# VGA-OSCI_SMD.net
KiCad netlist of a schematic drawn in EAGLE
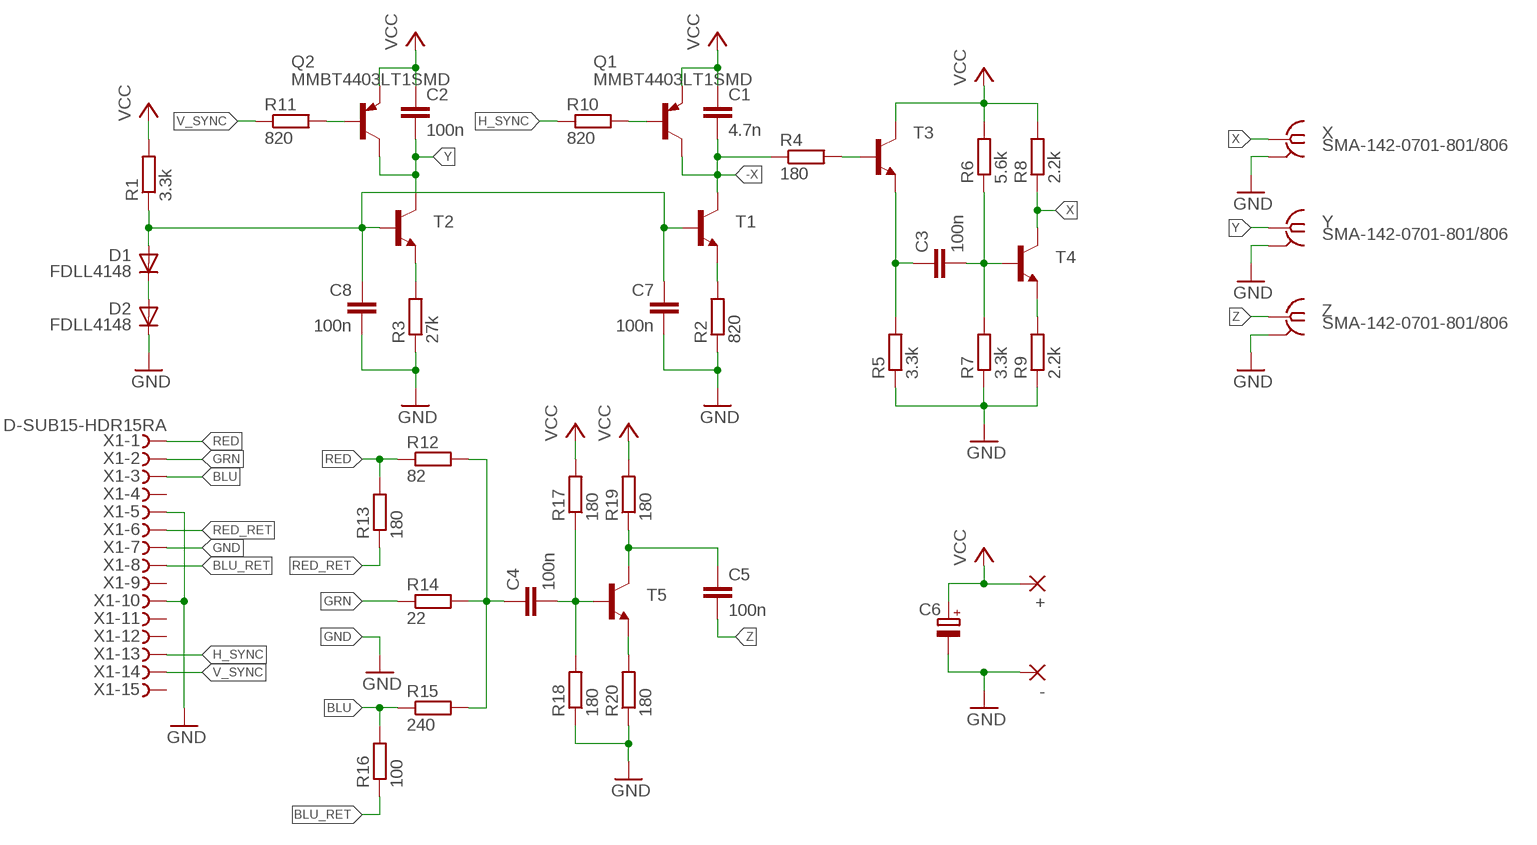
[diagram p0: schematic, sheet 1]

(export (version "E")
  (design (tool "Eeschema 10.0.6"))
  (components
    (comp (ref "+")
      (value "WIREPADSMD1,27-254")
      (footprint "eagle-import:SMD1,27-2,54")
      (libsource (lib "eagle-import") (part "WIREPADSMD1,27-254"))
    )
    (comp (ref "-")
      (value "WIREPADSMD1,27-254")
      (footprint "eagle-import:SMD1,27-2,54")
      (libsource (lib "eagle-import") (part "WIREPADSMD1,27-254"))
    )
    (comp (ref "C1")
      (value "4.7n")
      (footprint "eagle-import:C0603")
      (libsource (lib "eagle-import") (part "C-EUC0603"))
    )
    (comp (ref "C2")
      (value "100n")
      (footprint "eagle-import:C0603")
      (libsource (lib "eagle-import") (part "C-EUC0603"))
    )
    (comp (ref "C3")
      (value "100n")
      (footprint "eagle-import:C0603")
      (libsource (lib "eagle-import") (part "C-EUC0603"))
    )
    (comp (ref "C4")
      (value "100n")
      (footprint "eagle-import:C0603")
      (libsource (lib "eagle-import") (part "C-EUC0603"))
    )
    (comp (ref "C5")
      (value "100n")
      (footprint "eagle-import:C0603")
      (libsource (lib "eagle-import") (part "C-EUC0603"))
    )
    (comp (ref "C6")
      (value "CPOL-EU153CLV-0810")
      (footprint "eagle-import:153CLV-0810")
      (libsource (lib "eagle-import") (part "CPOL-EU153CLV-0810"))
    )
    (comp (ref "C7")
      (value "100n")
      (footprint "eagle-import:C0603")
      (libsource (lib "eagle-import") (part "C-EUC0603"))
    )
    (comp (ref "C8")
      (value "100n")
      (footprint "eagle-import:C0603")
      (libsource (lib "eagle-import") (part "C-EUC0603"))
    )
    (comp (ref "D1")
      (value "FDLL4148")
      (footprint "eagle-import:SOD80C")
      (libsource (lib "eagle-import") (part "DIODE-SOD80C"))
    )
    (comp (ref "D2")
      (value "FDLL4148")
      (footprint "eagle-import:SOD80C")
      (libsource (lib "eagle-import") (part "DIODE-SOD80C"))
    )
    (comp (ref "Q1")
      (value "MMBT4403LT1SMD")
      (footprint "eagle-import:SOT23-BEC")
      (libsource (lib "eagle-import") (part "-PNP-SOT23-BECMMBT4403LT1"))
    )
    (comp (ref "Q2")
      (value "MMBT4403LT1SMD")
      (footprint "eagle-import:SOT23-BEC")
      (libsource (lib "eagle-import") (part "-PNP-SOT23-BECMMBT4403LT1"))
    )
    (comp (ref "R1")
      (value "3.3k")
      (footprint "eagle-import:R0603")
      (libsource (lib "eagle-import") (part "R-EU_R0603"))
    )
    (comp (ref "R2")
      (value "820")
      (footprint "eagle-import:R0603")
      (libsource (lib "eagle-import") (part "R-EU_R0603"))
    )
    (comp (ref "R3")
      (value "27k")
      (footprint "eagle-import:R0603")
      (libsource (lib "eagle-import") (part "R-EU_R0603"))
    )
    (comp (ref "R4")
      (value "180")
      (footprint "eagle-import:R0603")
      (libsource (lib "eagle-import") (part "R-EU_R0603"))
    )
    (comp (ref "R5")
      (value "3.3k")
      (footprint "eagle-import:R0603")
      (libsource (lib "eagle-import") (part "R-EU_R0603"))
    )
    (comp (ref "R6")
      (value "5.6k")
      (footprint "eagle-import:R0603")
      (libsource (lib "eagle-import") (part "R-EU_R0603"))
    )
    (comp (ref "R7")
      (value "3.3k")
      (footprint "eagle-import:R0603")
      (libsource (lib "eagle-import") (part "R-EU_R0603"))
    )
    (comp (ref "R8")
      (value "2.2k")
      (footprint "eagle-import:R0603")
      (libsource (lib "eagle-import") (part "R-EU_R0603"))
    )
    (comp (ref "R9")
      (value "2.2k")
      (footprint "eagle-import:R0603")
      (libsource (lib "eagle-import") (part "R-EU_R0603"))
    )
    (comp (ref "R10")
      (value "820")
      (footprint "eagle-import:R0603")
      (libsource (lib "eagle-import") (part "R-EU_R0603"))
    )
    (comp (ref "R11")
      (value "820")
      (footprint "eagle-import:R0603")
      (libsource (lib "eagle-import") (part "R-EU_R0603"))
    )
    (comp (ref "R12")
      (value "82")
      (footprint "eagle-import:R0603")
      (libsource (lib "eagle-import") (part "R-EU_R0603"))
    )
    (comp (ref "R13")
      (value "180")
      (footprint "eagle-import:R0603")
      (libsource (lib "eagle-import") (part "R-EU_R0603"))
    )
    (comp (ref "R14")
      (value "22")
      (footprint "eagle-import:R0603")
      (libsource (lib "eagle-import") (part "R-EU_R0603"))
    )
    (comp (ref "R15")
      (value "240")
      (footprint "eagle-import:R0603")
      (libsource (lib "eagle-import") (part "R-EU_R0603"))
    )
    (comp (ref "R16")
      (value "100")
      (footprint "eagle-import:R0603")
      (libsource (lib "eagle-import") (part "R-EU_R0603"))
    )
    (comp (ref "R17")
      (value "180")
      (footprint "eagle-import:R0603")
      (libsource (lib "eagle-import") (part "R-EU_R0603"))
    )
    (comp (ref "R18")
      (value "180")
      (footprint "eagle-import:R0603")
      (libsource (lib "eagle-import") (part "R-EU_R0603"))
    )
    (comp (ref "R19")
      (value "180")
      (footprint "eagle-import:R0603")
      (libsource (lib "eagle-import") (part "R-EU_R0603"))
    )
    (comp (ref "R20")
      (value "180")
      (footprint "eagle-import:R0603")
      (libsource (lib "eagle-import") (part "R-EU_R0603"))
    )
    (comp (ref "T1")
      (value "MMBT2222ALT1-NPN-SOT23-BEC")
      (footprint "eagle-import:SOT23-BEC")
      (libsource (lib "eagle-import") (part "-NPN-SOT23-BECMMBT2222ALT1"))
    )
    (comp (ref "T2")
      (value "MMBT2222ALT1-NPN-SOT23-BEC")
      (footprint "eagle-import:SOT23-BEC")
      (libsource (lib "eagle-import") (part "-NPN-SOT23-BECMMBT2222ALT1"))
    )
    (comp (ref "T3")
      (value "MMBT2222ALT1-NPN-SOT23-BEC")
      (footprint "eagle-import:SOT23-BEC")
      (libsource (lib "eagle-import") (part "-NPN-SOT23-BECMMBT2222ALT1"))
    )
    (comp (ref "T4")
      (value "MMBT2222ALT1-NPN-SOT23-BEC")
      (footprint "eagle-import:SOT23-BEC")
      (libsource (lib "eagle-import") (part "-NPN-SOT23-BECMMBT2222ALT1"))
    )
    (comp (ref "T5")
      (value "MMBT2222ALT1-NPN-SOT23-BEC")
      (footprint "eagle-import:SOT23-BEC")
      (libsource (lib "eagle-import") (part "-NPN-SOT23-BECMMBT2222ALT1"))
    )
    (comp (ref "X")
      (value "SMA-142-0701-801/806")
      (footprint "eagle-import:J502-ND-142-0701-801_806")
      (fields (field (name "MF") "JOHNSON COMPONENTS") (field (name "MPN") "142-0701-801"))
      (libsource (lib "eagle-import") (part "SMA-142-0701-801/806"))
    )
    (comp (ref "X1")
      (value "D-SUB15-HDR15RA")
      (footprint "eagle-import:HDR15RA")
      (libsource (lib "eagle-import") (part "D-SUB15-HDR15RA"))
    )
    (comp (ref "Y")
      (value "SMA-142-0701-801/806")
      (footprint "eagle-import:J502-ND-142-0701-801_806")
      (fields (field (name "MF") "JOHNSON COMPONENTS") (field (name "MPN") "142-0701-801"))
      (libsource (lib "eagle-import") (part "SMA-142-0701-801/806"))
    )
    (comp (ref "Z")
      (value "SMA-142-0701-801/806")
      (footprint "eagle-import:J502-ND-142-0701-801_806")
      (fields (field (name "MF") "JOHNSON COMPONENTS") (field (name "MPN") "142-0701-801"))
      (libsource (lib "eagle-import") (part "SMA-142-0701-801/806"))
    )
  )
  (nets
    (net (code "1") (name "-X") (class "Default")
      (node (ref "C1") (pin "2") (pinfunction "2_2") (pintype "passive"))
      (node (ref "Q1") (pin "C") (pinfunction "C_C") (pintype "passive"))
      (node (ref "R4") (pin "1") (pinfunction "1_1") (pintype "passive"))
      (node (ref "T1") (pin "C") (pinfunction "C_C") (pintype "passive"))
    )
    (net (code "2") (name "BLU") (class "Default")
      (node (ref "R15") (pin "1") (pinfunction "1_1") (pintype "passive"))
      (node (ref "R16") (pin "2") (pinfunction "2_2") (pintype "passive"))
      (node (ref "X1") (pin "3") (pinfunction "F_3") (pintype "passive"))
    )
    (net (code "3") (name "BLU_RET") (class "Default")
      (node (ref "R16") (pin "1") (pinfunction "1_1") (pintype "passive"))
      (node (ref "X1") (pin "8") (pinfunction "F_8") (pintype "passive"))
    )
    (net (code "4") (name "GND") (class "Default")
      (node (ref "-") (pin "1") (pinfunction "P_1") (pintype "passive"))
      (node (ref "C6") (pin "-") (pinfunction "-_-") (pintype "passive"))
      (node (ref "C7") (pin "2") (pinfunction "2_2") (pintype "passive"))
      (node (ref "C8") (pin "2") (pinfunction "2_2") (pintype "passive"))
      (node (ref "D2") (pin "C") (pinfunction "C_C") (pintype "passive"))
      (node (ref "R18") (pin "1") (pinfunction "1_1") (pintype "passive"))
      (node (ref "R2") (pin "1") (pinfunction "1_1") (pintype "passive"))
      (node (ref "R20") (pin "1") (pinfunction "1_1") (pintype "passive"))
      (node (ref "R3") (pin "1") (pinfunction "1_1") (pintype "passive"))
      (node (ref "R5") (pin "1") (pinfunction "1_1") (pintype "passive"))
      (node (ref "R7") (pin "1") (pinfunction "1_1") (pintype "passive"))
      (node (ref "R9") (pin "1") (pinfunction "1_1") (pintype "passive"))
      (node (ref "X") (pin "G@1") (pinfunction "2_G@1") (pintype "passive"))
      (node (ref "X") (pin "G@2") (pinfunction "2_G@2") (pintype "passive"))
      (node (ref "X") (pin "G@3") (pinfunction "2_G@3") (pintype "passive"))
      (node (ref "X") (pin "G@4") (pinfunction "2_G@4") (pintype "passive"))
      (node (ref "X1") (pin "10") (pinfunction "F_10") (pintype "passive"))
      (node (ref "X1") (pin "5") (pinfunction "F_5") (pintype "passive"))
      (node (ref "X1") (pin "7") (pinfunction "F_7") (pintype "passive"))
      (node (ref "Y") (pin "G@1") (pinfunction "2_G@1") (pintype "passive"))
      (node (ref "Y") (pin "G@2") (pinfunction "2_G@2") (pintype "passive"))
      (node (ref "Y") (pin "G@3") (pinfunction "2_G@3") (pintype "passive"))
      (node (ref "Y") (pin "G@4") (pinfunction "2_G@4") (pintype "passive"))
      (node (ref "Z") (pin "G@1") (pinfunction "2_G@1") (pintype "passive"))
      (node (ref "Z") (pin "G@2") (pinfunction "2_G@2") (pintype "passive"))
      (node (ref "Z") (pin "G@3") (pinfunction "2_G@3") (pintype "passive"))
      (node (ref "Z") (pin "G@4") (pinfunction "2_G@4") (pintype "passive"))
    )
    (net (code "5") (name "GRN") (class "Default")
      (node (ref "R14") (pin "1") (pinfunction "1_1") (pintype "passive"))
      (node (ref "X1") (pin "2") (pinfunction "F_2") (pintype "passive"))
    )
    (net (code "6") (name "H_SYNC") (class "Default")
      (node (ref "R10") (pin "1") (pinfunction "1_1") (pintype "passive"))
      (node (ref "X1") (pin "13") (pinfunction "F_13") (pintype "passive"))
    )
    (net (code "7") (name "Net-(C3-Pad1)") (class "Default")
      (node (ref "C3") (pin "1") (pinfunction "1_1") (pintype "passive"))
      (node (ref "R5") (pin "2") (pinfunction "2_2") (pintype "passive"))
      (node (ref "T3") (pin "E") (pinfunction "E_E") (pintype "passive"))
    )
    (net (code "8") (name "Net-(C3-Pad2)") (class "Default")
      (node (ref "C3") (pin "2") (pinfunction "2_2") (pintype "passive"))
      (node (ref "R6") (pin "1") (pinfunction "1_1") (pintype "passive"))
      (node (ref "R7") (pin "2") (pinfunction "2_2") (pintype "passive"))
      (node (ref "T4") (pin "B") (pinfunction "B_B") (pintype "passive"))
    )
    (net (code "9") (name "Net-(C4-Pad1)") (class "Default")
      (node (ref "C4") (pin "1") (pinfunction "1_1") (pintype "passive"))
      (node (ref "R12") (pin "2") (pinfunction "2_2") (pintype "passive"))
      (node (ref "R14") (pin "2") (pinfunction "2_2") (pintype "passive"))
      (node (ref "R15") (pin "2") (pinfunction "2_2") (pintype "passive"))
    )
    (net (code "10") (name "Net-(C4-Pad2)") (class "Default")
      (node (ref "C4") (pin "2") (pinfunction "2_2") (pintype "passive"))
      (node (ref "R17") (pin "1") (pinfunction "1_1") (pintype "passive"))
      (node (ref "R18") (pin "2") (pinfunction "2_2") (pintype "passive"))
      (node (ref "T5") (pin "B") (pinfunction "B_B") (pintype "passive"))
    )
    (net (code "11") (name "Net-(C5-Pad1)") (class "Default")
      (node (ref "C5") (pin "1") (pinfunction "1_1") (pintype "passive"))
      (node (ref "R19") (pin "1") (pinfunction "1_1") (pintype "passive"))
      (node (ref "T5") (pin "C") (pinfunction "C_C") (pintype "passive"))
    )
    (net (code "12") (name "Net-(C7-Pad1)") (class "Default")
      (node (ref "C7") (pin "1") (pinfunction "1_1") (pintype "passive"))
      (node (ref "C8") (pin "1") (pinfunction "1_1") (pintype "passive"))
      (node (ref "D1") (pin "A") (pinfunction "A_A") (pintype "passive"))
      (node (ref "R1") (pin "1") (pinfunction "1_1") (pintype "passive"))
      (node (ref "T1") (pin "B") (pinfunction "B_B") (pintype "passive"))
      (node (ref "T2") (pin "B") (pinfunction "B_B") (pintype "passive"))
    )
    (net (code "13") (name "Net-(D1-PadC)") (class "Default")
      (node (ref "D1") (pin "C") (pinfunction "C_C") (pintype "passive"))
      (node (ref "D2") (pin "A") (pinfunction "A_A") (pintype "passive"))
    )
    (net (code "14") (name "Net-(Q1-PadB)") (class "Default")
      (node (ref "Q1") (pin "B") (pinfunction "B_B") (pintype "passive"))
      (node (ref "R10") (pin "2") (pinfunction "2_2") (pintype "passive"))
    )
    (net (code "15") (name "Net-(Q2-PadB)") (class "Default")
      (node (ref "Q2") (pin "B") (pinfunction "B_B") (pintype "passive"))
      (node (ref "R11") (pin "2") (pinfunction "2_2") (pintype "passive"))
    )
    (net (code "16") (name "Net-(R2-Pad2)") (class "Default")
      (node (ref "R2") (pin "2") (pinfunction "2_2") (pintype "passive"))
      (node (ref "T1") (pin "E") (pinfunction "E_E") (pintype "passive"))
    )
    (net (code "17") (name "Net-(R3-Pad2)") (class "Default")
      (node (ref "R3") (pin "2") (pinfunction "2_2") (pintype "passive"))
      (node (ref "T2") (pin "E") (pinfunction "E_E") (pintype "passive"))
    )
    (net (code "18") (name "Net-(R4-Pad2)") (class "Default")
      (node (ref "R4") (pin "2") (pinfunction "2_2") (pintype "passive"))
      (node (ref "T3") (pin "B") (pinfunction "B_B") (pintype "passive"))
    )
    (net (code "19") (name "Net-(R9-Pad2)") (class "Default")
      (node (ref "R9") (pin "2") (pinfunction "2_2") (pintype "passive"))
      (node (ref "T4") (pin "E") (pinfunction "E_E") (pintype "passive"))
    )
    (net (code "20") (name "Net-(R20-Pad2)") (class "Default")
      (node (ref "R20") (pin "2") (pinfunction "2_2") (pintype "passive"))
      (node (ref "T5") (pin "E") (pinfunction "E_E") (pintype "passive"))
    )
    (net (code "21") (name "RED") (class "Default")
      (node (ref "R12") (pin "1") (pinfunction "1_1") (pintype "passive"))
      (node (ref "R13") (pin "2") (pinfunction "2_2") (pintype "passive"))
      (node (ref "X1") (pin "1") (pinfunction "F_1") (pintype "passive"))
    )
    (net (code "22") (name "RED_RET") (class "Default")
      (node (ref "R13") (pin "1") (pinfunction "1_1") (pintype "passive"))
      (node (ref "X1") (pin "6") (pinfunction "F_6") (pintype "passive"))
    )
    (net (code "23") (name "VCC") (class "Default")
      (node (ref "+") (pin "1") (pinfunction "P_1") (pintype "passive"))
      (node (ref "C1") (pin "1") (pinfunction "1_1") (pintype "passive"))
      (node (ref "C2") (pin "1") (pinfunction "1_1") (pintype "passive"))
      (node (ref "C6") (pin "+") (pinfunction "+_+") (pintype "passive"))
      (node (ref "Q1") (pin "E") (pinfunction "E_E") (pintype "passive"))
      (node (ref "Q2") (pin "E") (pinfunction "E_E") (pintype "passive"))
      (node (ref "R1") (pin "2") (pinfunction "2_2") (pintype "passive"))
      (node (ref "R17") (pin "2") (pinfunction "2_2") (pintype "passive"))
      (node (ref "R19") (pin "2") (pinfunction "2_2") (pintype "passive"))
      (node (ref "R6") (pin "2") (pinfunction "2_2") (pintype "passive"))
      (node (ref "R8") (pin "2") (pinfunction "2_2") (pintype "passive"))
      (node (ref "T3") (pin "C") (pinfunction "C_C") (pintype "passive"))
    )
    (net (code "24") (name "V_SYNC") (class "Default")
      (node (ref "R11") (pin "1") (pinfunction "1_1") (pintype "passive"))
      (node (ref "X1") (pin "14") (pinfunction "F_14") (pintype "passive"))
    )
    (net (code "25") (name "X") (class "Default")
      (node (ref "R8") (pin "1") (pinfunction "1_1") (pintype "passive"))
      (node (ref "T4") (pin "C") (pinfunction "C_C") (pintype "passive"))
      (node (ref "X") (pin "1") (pinfunction "1_1") (pintype "passive"))
    )
    (net (code "26") (name "Y") (class "Default")
      (node (ref "C2") (pin "2") (pinfunction "2_2") (pintype "passive"))
      (node (ref "Q2") (pin "C") (pinfunction "C_C") (pintype "passive"))
      (node (ref "T2") (pin "C") (pinfunction "C_C") (pintype "passive"))
      (node (ref "Y") (pin "1") (pinfunction "1_1") (pintype "passive"))
    )
    (net (code "27") (name "Z") (class "Default")
      (node (ref "C5") (pin "2") (pinfunction "2_2") (pintype "passive"))
      (node (ref "Z") (pin "1") (pinfunction "1_1") (pintype "passive"))
    )
    (net (code "28") (name "unconnected-(X1C-F-Pad11)") (class "Default")
      (node (ref "X1") (pin "11") (pinfunction "F_11") (pintype "passive"))
    )
    (net (code "29") (name "unconnected-(X1D-F-Pad12)") (class "Default")
      (node (ref "X1") (pin "12") (pinfunction "F_12") (pintype "passive"))
    )
    (net (code "30") (name "unconnected-(X1G-F-Pad15)") (class "Default")
      (node (ref "X1") (pin "15") (pinfunction "F_15") (pintype "passive"))
    )
    (net (code "31") (name "unconnected-(X1J-F-Pad4)") (class "Default")
      (node (ref "X1") (pin "4") (pinfunction "F_4") (pintype "passive"))
    )
    (net (code "32") (name "unconnected-(X1O-F-Pad9)") (class "Default")
      (node (ref "X1") (pin "9") (pinfunction "F_9") (pintype "passive"))
    )
  )
)
